# Inputs.net
KiCad netlist of a schematic drawn in Altium Designer
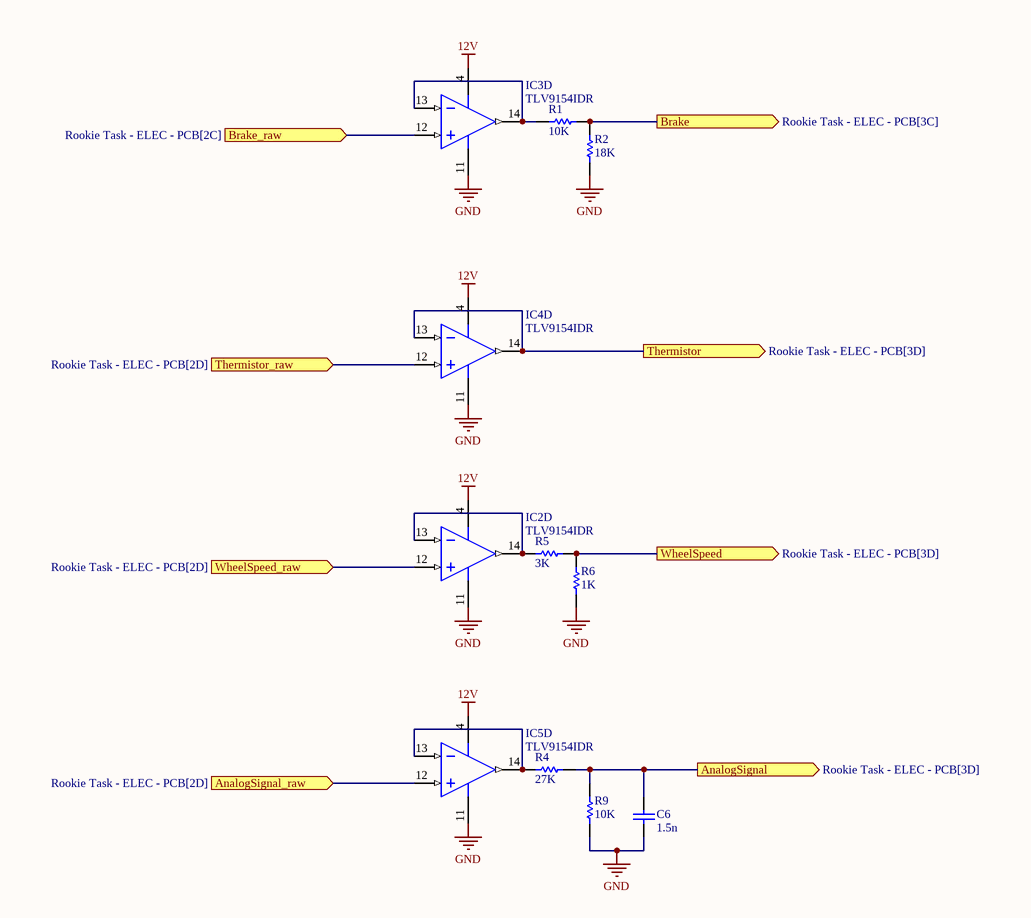
[diagram p0: Inputs.SchDoc]

(export (version "E")
  (design (tool "Eeschema 10.0.6"))
  (components
    (comp (ref "C6")
      (value "1.5n")
      (description "Capacitor")
      (libsource (lib "Simulation Generic Components") (part "Capacitor"))
    )
    (comp (ref "IC2")
      (value "TLV9154IDR")
      (footprint "SOIC127P600X175-14N")
      (description "Texas Instruments 16-V")
      (fields (field (name "MOUSER PART NUMBER") "595-TLV9154IDR"))
      (libsource (lib "Americas- Concordia Electric Formula Racing") (part "TLV9154IDR"))
    )
    (comp (ref "IC3")
      (value "TLV9154IDR")
      (footprint "SOIC127P600X175-14N")
      (description "Texas Instruments 16-V")
      (fields (field (name "MOUSER PART NUMBER") "595-TLV9154IDR"))
      (libsource (lib "Americas- Concordia Electric Formula Racing") (part "TLV9154IDR"))
    )
    (comp (ref "IC4")
      (value "TLV9154IDR")
      (footprint "SOIC127P600X175-14N")
      (description "Texas Instruments 16-V")
      (fields (field (name "MOUSER PART NUMBER") "595-TLV9154IDR"))
      (libsource (lib "Americas- Concordia Electric Formula Racing") (part "TLV9154IDR"))
    )
    (comp (ref "IC5")
      (value "TLV9154IDR")
      (footprint "SOIC127P600X175-14N")
      (description "Texas Instruments 16-V")
      (fields (field (name "MOUSER PART NUMBER") "595-TLV9154IDR"))
      (libsource (lib "Americas- Concordia Electric Formula Racing") (part "TLV9154IDR"))
    )
    (comp (ref "R1")
      (value "10K")
      (description "Resistor")
      (libsource (lib "Simulation Generic Components") (part "Resistor"))
    )
    (comp (ref "R2")
      (value "18K")
      (description "Resistor")
      (libsource (lib "Simulation Generic Components") (part "Resistor"))
    )
    (comp (ref "R4")
      (value "27K")
      (description "Resistor")
      (libsource (lib "Simulation Generic Components") (part "Resistor"))
    )
    (comp (ref "R5")
      (value "3K")
      (description "Resistor")
      (libsource (lib "Simulation Generic Components") (part "Resistor"))
    )
    (comp (ref "R6")
      (value "1K")
      (description "Resistor")
      (libsource (lib "Simulation Generic Components") (part "Resistor"))
    )
    (comp (ref "R9")
      (value "10K")
      (description "Resistor")
      (libsource (lib "Simulation Generic Components") (part "Resistor"))
    )
  )
  (nets
    (net (code "1") (name "/AnalogSignal") (class "Default")
      (node (ref "C6") (pin "2") (pinfunction "2_2") (pintype "passive"))
      (node (ref "R4") (pin "2") (pinfunction "2_2") (pintype "passive"))
      (node (ref "R9") (pin "2") (pinfunction "2_2") (pintype "passive"))
    )
    (net (code "2") (name "/AnalogSignal_raw") (class "Default")
      (node (ref "IC5") (pin "12") (pinfunction "VIND+_12") (pintype "input"))
    )
    (net (code "3") (name "/Brake") (class "Default")
      (node (ref "R1") (pin "2") (pinfunction "2_2") (pintype "passive"))
      (node (ref "R2") (pin "2") (pinfunction "2_2") (pintype "passive"))
    )
    (net (code "4") (name "/Brake_raw") (class "Default")
      (node (ref "IC3") (pin "12") (pinfunction "VIND+_12") (pintype "input"))
    )
    (net (code "5") (name "/Thermistor") (class "Default")
      (node (ref "IC4") (pin "13") (pinfunction "VIND-_13") (pintype "input"))
      (node (ref "IC4") (pin "14") (pinfunction "VOUTD_14") (pintype "output"))
    )
    (net (code "6") (name "/Thermistor_raw") (class "Default")
      (node (ref "IC4") (pin "12") (pinfunction "VIND+_12") (pintype "input"))
    )
    (net (code "7") (name "/WheelSpeed") (class "Default")
      (node (ref "R5") (pin "2") (pinfunction "2_2") (pintype "passive"))
      (node (ref "R6") (pin "2") (pinfunction "2_2") (pintype "passive"))
    )
    (net (code "8") (name "/WheelSpeed_raw") (class "Default")
      (node (ref "IC2") (pin "12") (pinfunction "VIND+_12") (pintype "input"))
    )
    (net (code "9") (name "12V") (class "Default")
      (node (ref "IC2") (pin "4") (pinfunction "VDD_4") (pintype "power_in"))
      (node (ref "IC3") (pin "4") (pinfunction "VDD_4") (pintype "power_in"))
      (node (ref "IC4") (pin "4") (pinfunction "VDD_4") (pintype "power_in"))
      (node (ref "IC5") (pin "4") (pinfunction "VDD_4") (pintype "power_in"))
    )
    (net (code "10") (name "GND") (class "Default")
      (node (ref "C6") (pin "1") (pinfunction "1_1") (pintype "passive"))
      (node (ref "IC2") (pin "11") (pinfunction "VSS_11") (pintype "power_in"))
      (node (ref "IC3") (pin "11") (pinfunction "VSS_11") (pintype "power_in"))
      (node (ref "IC4") (pin "11") (pinfunction "VSS_11") (pintype "power_in"))
      (node (ref "IC5") (pin "11") (pinfunction "VSS_11") (pintype "power_in"))
      (node (ref "R2") (pin "1") (pinfunction "1_1") (pintype "passive"))
      (node (ref "R6") (pin "1") (pinfunction "1_1") (pintype "passive"))
      (node (ref "R9") (pin "1") (pinfunction "1_1") (pintype "passive"))
    )
    (net (code "11") (name "Net-(IC2D-VIND-)") (class "Default")
      (node (ref "IC2") (pin "13") (pinfunction "VIND-_13") (pintype "input"))
      (node (ref "IC2") (pin "14") (pinfunction "VOUTD_14") (pintype "output"))
      (node (ref "R5") (pin "1") (pinfunction "1_1") (pintype "passive"))
    )
    (net (code "12") (name "Net-(IC3D-VIND-)") (class "Default")
      (node (ref "IC3") (pin "13") (pinfunction "VIND-_13") (pintype "input"))
      (node (ref "IC3") (pin "14") (pinfunction "VOUTD_14") (pintype "output"))
      (node (ref "R1") (pin "1") (pinfunction "1_1") (pintype "passive"))
    )
    (net (code "13") (name "Net-(IC5D-VIND-)") (class "Default")
      (node (ref "IC5") (pin "13") (pinfunction "VIND-_13") (pintype "input"))
      (node (ref "IC5") (pin "14") (pinfunction "VOUTD_14") (pintype "output"))
      (node (ref "R4") (pin "1") (pinfunction "1_1") (pintype "passive"))
    )
  )
)
